# Buck_3V3.net
KiCad netlist of a schematic drawn in Altium Designer
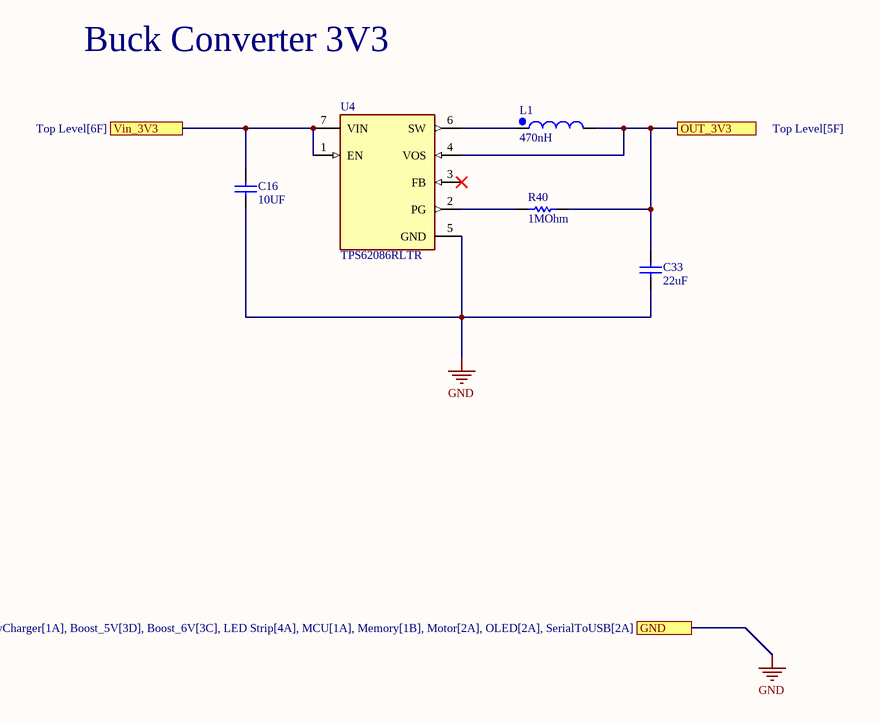
[diagram p0: Buck_3V3.SchDoc]

(export (version "E")
  (design (tool "Eeschema 10.0.6"))
  (components
    (comp (ref "C16")
      (value "10UF")
      (footprint "0603_CAP")
      (description "Capacitor Surface Mount 0603 Footprint 10UF 16V 20% Tolerance Ceramic X5R")
      (fields (field (name "MANUFACTURER") "Various") (field (name "TOLERANCE") "20%"))
      (libsource (lib "University of Pennsylvania (ESE)") (part "cap"))
    )
    (comp (ref "C33")
      (value "22uF")
      (footprint "0805_CAP_60H")
      (description "Capacitor Surface Mount 0805 Footprint 22UF 10V 20% Tolerance Ceramic X5R")
      (fields (field (name "TOLERANCE") "20%") (field (name "MANUFACTURER") "Various"))
      (libsource (lib "University of Pennsylvania (ESE)") (part "cap"))
    )
    (comp (ref "L1")
      (value "470nH")
      (footprint "WE-LHMI_5030")
      (description "General Purpose Inductor, 0.47uH, 20%, 1 Element, Powdered  Iron-Core, SMD, 2220")
      (fields (field (name "Comment") "744373360047"))
      (libsource (lib "University of Pennsylvania (ESE)") (part "INDUCTOR"))
    )
    (comp (ref "R40")
      (value "1MOhm")
      (footprint "RESC1608X55X25LL10T15")
      (description "Chip Resistor, 1 MOhm, +/- 1%, 100 mW, -55 to 155 degC, 0603 (1608 Metric), RoHS, Tape and Reel")
      (fields (field (name "TOLERANCE") "20%"))
      (libsource (lib "Altium Content Vault") (part "RES-2"))
    )
    (comp (ref "U4")
      (value "TPS62086RLTR")
      (footprint "FP-RLT0007A-MFG")
      (description "IC REG BUCK 3.3V 3A 7VSON-HR")
      (libsource (lib "Altium Content Vault") (part "4e7eb6474dc88d883a1c2f1f1891d8c"))
    )
  )
  (nets
    (net (code "1") (name "/OUT_3V3") (class "Default")
      (node (ref "C33") (pin "2") (pinfunction "2_2") (pintype "passive"))
      (node (ref "L1") (pin "2") (pinfunction "2_2") (pintype "passive"))
      (node (ref "R40") (pin "2") (pinfunction "2_2") (pintype "passive"))
      (node (ref "U4") (pin "4") (pinfunction "VOS_4") (pintype "input"))
    )
    (net (code "2") (name "/Vin_3V3") (class "Default")
      (node (ref "C16") (pin "2") (pinfunction "2_2") (pintype "passive"))
      (node (ref "U4") (pin "1") (pinfunction "EN_1") (pintype "input"))
      (node (ref "U4") (pin "7") (pinfunction "VIN_7") (pintype "power_in"))
    )
    (net (code "3") (name "GND") (class "Default")
      (node (ref "C16") (pin "1") (pinfunction "1_1") (pintype "passive"))
      (node (ref "C33") (pin "1") (pinfunction "1_1") (pintype "passive"))
      (node (ref "U4") (pin "5") (pinfunction "GND_5") (pintype "power_in"))
    )
    (net (code "4") (name "Net-(U4-PG)") (class "Default")
      (node (ref "R40") (pin "1") (pinfunction "1_1") (pintype "passive"))
      (node (ref "U4") (pin "2") (pinfunction "PG_2") (pintype "output"))
    )
    (net (code "5") (name "Net-(U4-SW)") (class "Default")
      (node (ref "L1") (pin "1") (pinfunction "1_1") (pintype "passive"))
      (node (ref "U4") (pin "6") (pinfunction "SW_6") (pintype "output"))
    )
    (net (code "6") (name "unconnected-(U4-FB-Pad3)") (class "Default")
      (node (ref "U4") (pin "3") (pinfunction "FB_3") (pintype "input+no_connect"))
    )
  )
)
